# MotorCtrl.net
KiCad netlist of a schematic drawn in Altium Designer
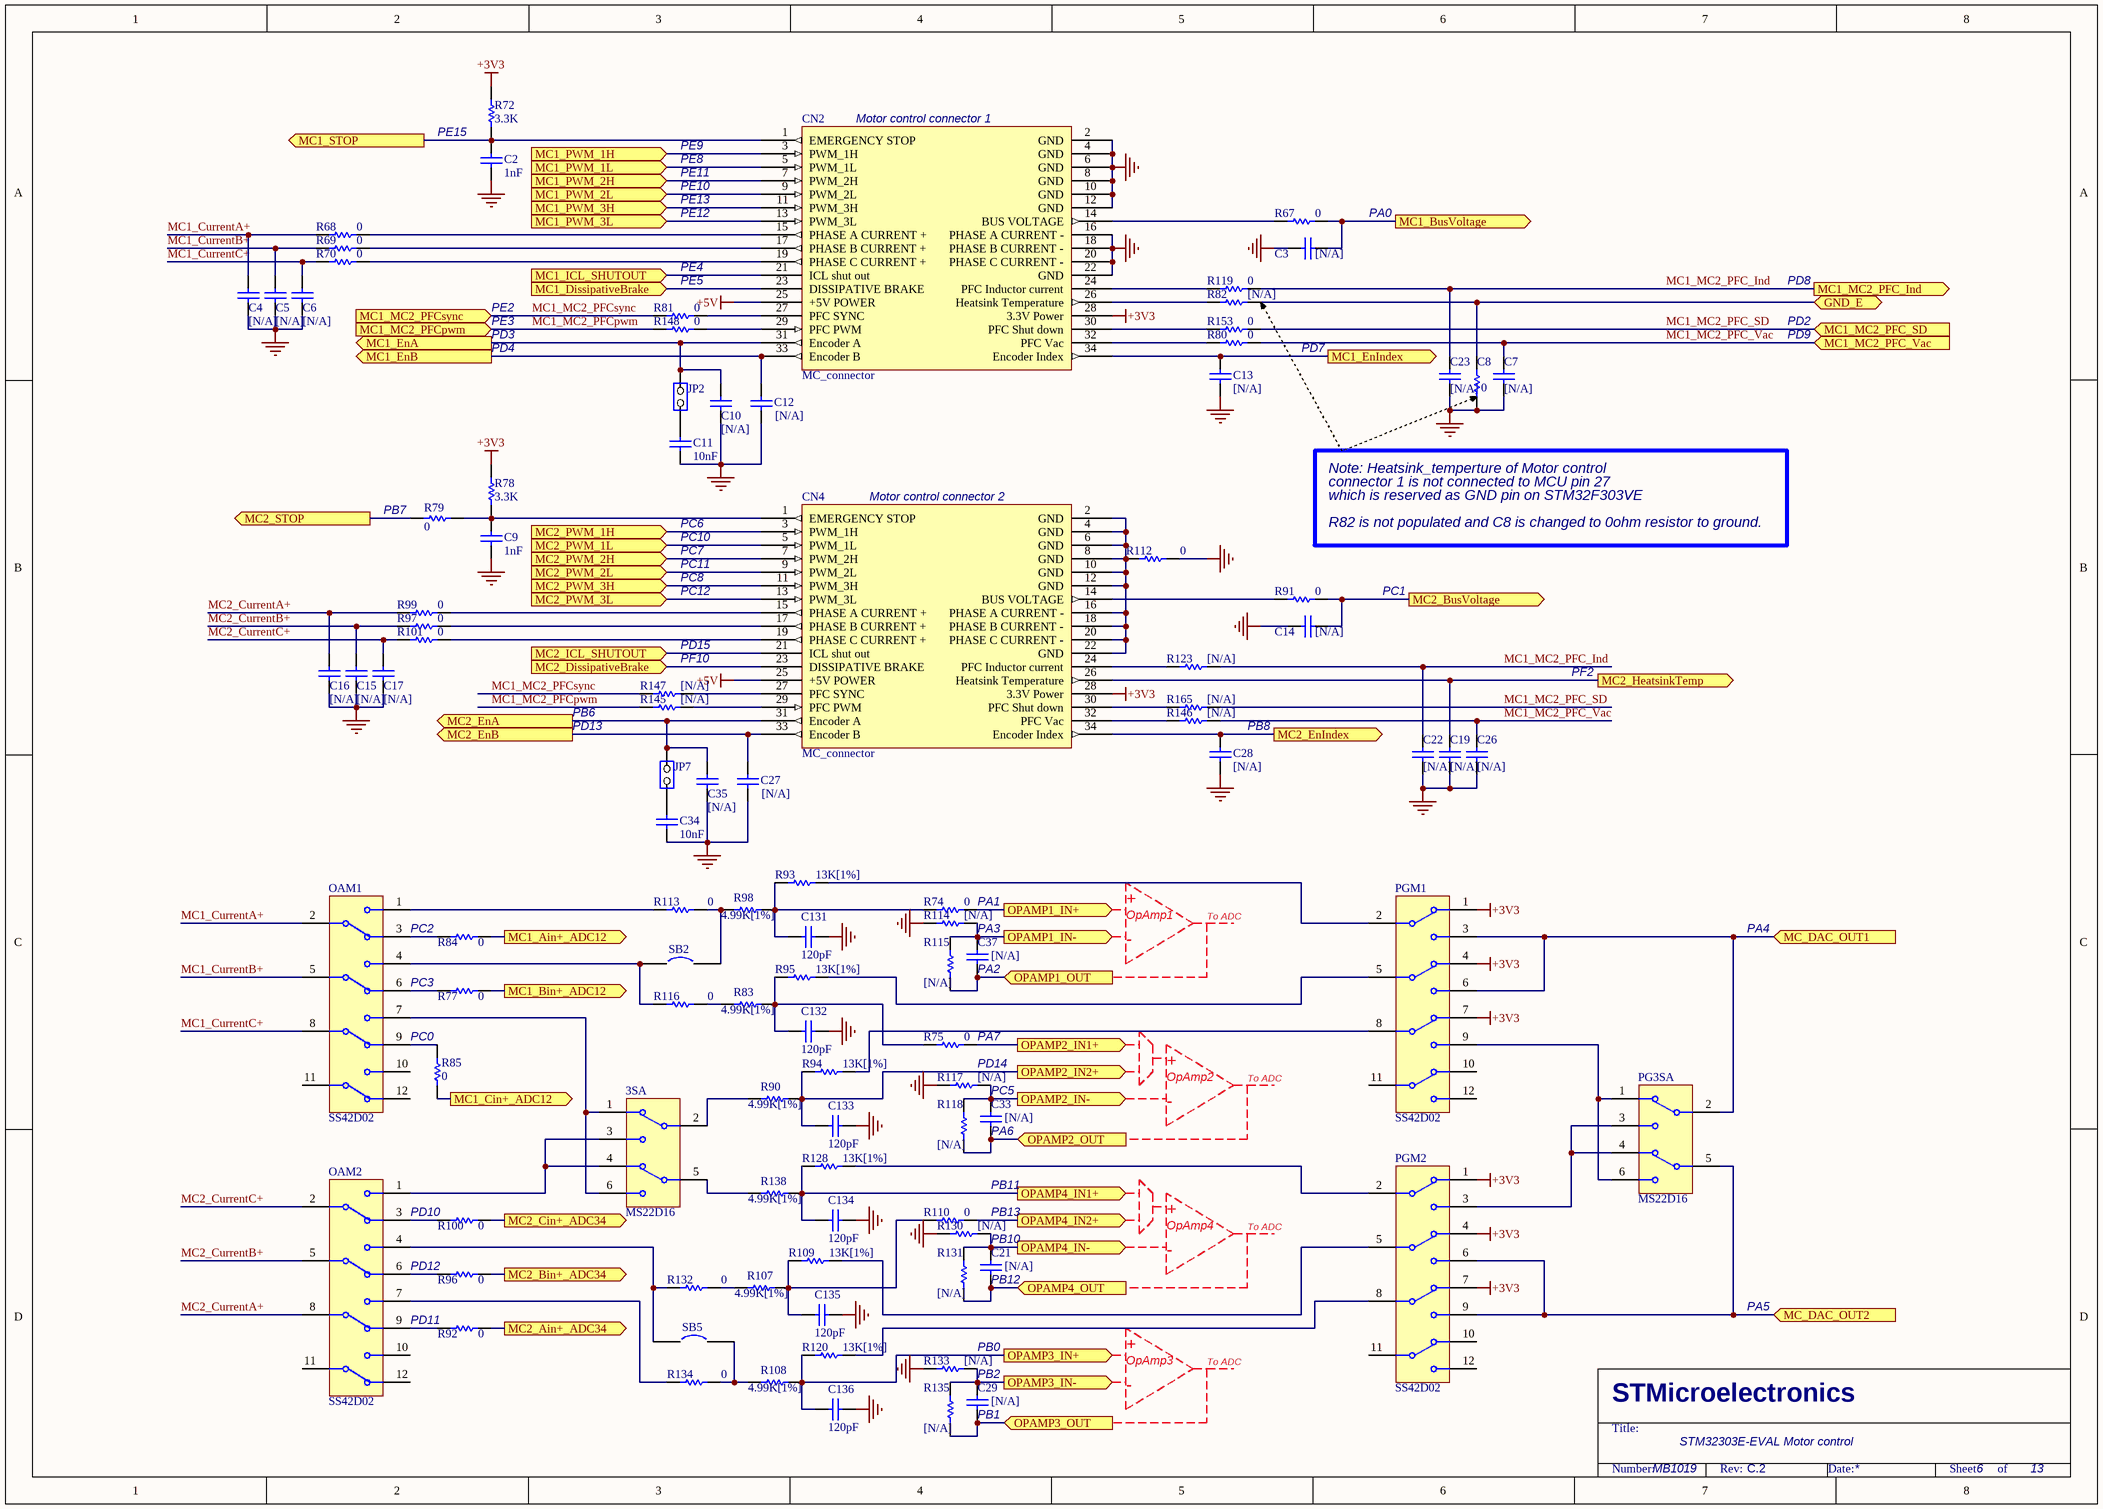
[diagram p0: MotorCtrl.SchDoc]

(export (version "E")
  (design (tool "Eeschema 10.0.6"))
  (components
    (comp (ref "3SA")
      (value "MS22D16")
      (footprint "MS22D16")
      (description "DPDT")
      (fields (field (name "PUBLISHER") "Altium Limited"))
      (libsource (lib "MB1019") (part "MS22D16"))
    )
    (comp (ref "C2")
      (value "1nF")
      (footprint "0603C")
      (description "Capacitor")
      (fields (field (name "PUBLISHER") "Altium Limited"))
      (libsource (lib "Miscellaneous Devices") (part "CAP"))
    )
    (comp (ref "C3")
      (value "[N/A]")
      (footprint "0603C")
      (description "Capacitor")
      (fields (field (name "PUBLISHER") "Altium Limited"))
      (libsource (lib "Miscellaneous Devices") (part "cap"))
    )
    (comp (ref "C4")
      (value "[N/A]")
      (footprint "0603C")
      (description "Capacitor")
      (fields (field (name "PUBLISHER") "Altium Limited"))
      (libsource (lib "Miscellaneous Devices") (part "cap"))
    )
    (comp (ref "C5")
      (value "[N/A]")
      (footprint "0603C")
      (description "Capacitor")
      (fields (field (name "PUBLISHER") "Altium Limited"))
      (libsource (lib "Miscellaneous Devices") (part "cap"))
    )
    (comp (ref "C6")
      (value "[N/A]")
      (footprint "0603C")
      (description "Capacitor")
      (fields (field (name "PUBLISHER") "Altium Limited"))
      (libsource (lib "Miscellaneous Devices") (part "cap"))
    )
    (comp (ref "C7")
      (value "[N/A]")
      (footprint "0603C")
      (description "Capacitor")
      (fields (field (name "PUBLISHER") "Altium Limited"))
      (libsource (lib "Miscellaneous Devices") (part "cap"))
    )
    (comp (ref "C8")
      (value "0")
      (footprint "0603R")
      (description "Resistor")
      (fields (field (name "PUBLISHER") "Altium Limited"))
      (libsource (lib "Miscellaneous Devices") (part "Res1"))
    )
    (comp (ref "C9")
      (value "1nF")
      (footprint "0603C")
      (description "Capacitor")
      (fields (field (name "PUBLISHER") "Altium Limited"))
      (libsource (lib "Miscellaneous Devices") (part "CAP"))
    )
    (comp (ref "C10")
      (value "[N/A]")
      (footprint "0603C")
      (description "Capacitor")
      (fields (field (name "PUBLISHER") "Altium Limited"))
      (libsource (lib "Miscellaneous Devices") (part "cap"))
    )
    (comp (ref "C11")
      (value "10nF")
      (footprint "0603C")
      (description "Capacitor")
      (fields (field (name "PUBLISHER") "Altium Limited"))
      (libsource (lib "Miscellaneous Devices") (part "cap"))
    )
    (comp (ref "C12")
      (value "[N/A]")
      (footprint "0603C")
      (description "Capacitor")
      (fields (field (name "PUBLISHER") "Altium Limited"))
      (libsource (lib "Miscellaneous Devices") (part "cap"))
    )
    (comp (ref "C13")
      (value "[N/A]")
      (footprint "0603C")
      (description "Capacitor")
      (fields (field (name "PUBLISHER") "Altium Limited"))
      (libsource (lib "Miscellaneous Devices") (part "cap"))
    )
    (comp (ref "C14")
      (value "[N/A]")
      (footprint "0603C")
      (description "Capacitor")
      (fields (field (name "PUBLISHER") "Altium Limited"))
      (libsource (lib "Miscellaneous Devices") (part "cap"))
    )
    (comp (ref "C15")
      (value "[N/A]")
      (footprint "0603C")
      (description "Capacitor")
      (fields (field (name "PUBLISHER") "Altium Limited"))
      (libsource (lib "Miscellaneous Devices") (part "cap"))
    )
    (comp (ref "C16")
      (value "[N/A]")
      (footprint "0603C")
      (description "Capacitor")
      (fields (field (name "PUBLISHER") "Altium Limited"))
      (libsource (lib "Miscellaneous Devices") (part "cap"))
    )
    (comp (ref "C17")
      (value "[N/A]")
      (footprint "0603C")
      (description "Capacitor")
      (fields (field (name "PUBLISHER") "Altium Limited"))
      (libsource (lib "Miscellaneous Devices") (part "cap"))
    )
    (comp (ref "C19")
      (value "[N/A]")
      (footprint "0603C")
      (description "Capacitor")
      (fields (field (name "PUBLISHER") "Altium Limited"))
      (libsource (lib "Miscellaneous Devices") (part "cap"))
    )
    (comp (ref "C21")
      (value "[N/A]")
      (footprint "0603C")
      (description "Capacitor")
      (fields (field (name "PUBLISHER") "Altium Limited"))
      (libsource (lib "Miscellaneous Devices") (part "cap"))
    )
    (comp (ref "C22")
      (value "[N/A]")
      (footprint "0603C")
      (description "Capacitor")
      (fields (field (name "PUBLISHER") "Altium Limited"))
      (libsource (lib "Miscellaneous Devices") (part "cap"))
    )
    (comp (ref "C23")
      (value "[N/A]")
      (footprint "0603C")
      (description "Capacitor")
      (fields (field (name "PUBLISHER") "Altium Limited"))
      (libsource (lib "Miscellaneous Devices") (part "cap"))
    )
    (comp (ref "C26")
      (value "[N/A]")
      (footprint "0603C")
      (description "Capacitor")
      (fields (field (name "PUBLISHER") "Altium Limited"))
      (libsource (lib "Miscellaneous Devices") (part "cap"))
    )
    (comp (ref "C27")
      (value "[N/A]")
      (footprint "0603C")
      (description "Capacitor")
      (fields (field (name "PUBLISHER") "Altium Limited"))
      (libsource (lib "Miscellaneous Devices") (part "cap"))
    )
    (comp (ref "C28")
      (value "[N/A]")
      (footprint "0603C")
      (description "Capacitor")
      (fields (field (name "PUBLISHER") "Altium Limited"))
      (libsource (lib "Miscellaneous Devices") (part "cap"))
    )
    (comp (ref "C29")
      (value "[N/A]")
      (footprint "0603C")
      (description "Capacitor")
      (fields (field (name "PUBLISHER") "Altium Limited"))
      (libsource (lib "Miscellaneous Devices") (part "cap"))
    )
    (comp (ref "C33")
      (value "[N/A]")
      (footprint "0603C")
      (description "Capacitor")
      (fields (field (name "PUBLISHER") "Altium Limited"))
      (libsource (lib "Miscellaneous Devices") (part "cap"))
    )
    (comp (ref "C34")
      (value "10nF")
      (footprint "0603C")
      (description "Capacitor")
      (fields (field (name "PUBLISHER") "Altium Limited"))
      (libsource (lib "Miscellaneous Devices") (part "cap"))
    )
    (comp (ref "C35")
      (value "[N/A]")
      (footprint "0603C")
      (description "Capacitor")
      (fields (field (name "PUBLISHER") "Altium Limited"))
      (libsource (lib "Miscellaneous Devices") (part "cap"))
    )
    (comp (ref "C37")
      (value "[N/A]")
      (footprint "0603C")
      (description "Capacitor")
      (fields (field (name "PUBLISHER") "Altium Limited"))
      (libsource (lib "Miscellaneous Devices") (part "cap"))
    )
    (comp (ref "C131")
      (value "120pF")
      (footprint "0603C")
      (description "Capacitor")
      (fields (field (name "PUBLISHER") "Altium Limited"))
      (libsource (lib "Miscellaneous Devices") (part "cap"))
    )
    (comp (ref "C132")
      (value "120pF")
      (footprint "0603C")
      (description "Capacitor")
      (fields (field (name "PUBLISHER") "Altium Limited"))
      (libsource (lib "Miscellaneous Devices") (part "cap"))
    )
    (comp (ref "C133")
      (value "120pF")
      (footprint "0603C")
      (description "Capacitor")
      (fields (field (name "PUBLISHER") "Altium Limited"))
      (libsource (lib "Miscellaneous Devices") (part "cap"))
    )
    (comp (ref "C134")
      (value "120pF")
      (footprint "0603C")
      (description "Capacitor")
      (fields (field (name "PUBLISHER") "Altium Limited"))
      (libsource (lib "Miscellaneous Devices") (part "cap"))
    )
    (comp (ref "C135")
      (value "120pF")
      (footprint "0603C")
      (description "Capacitor")
      (fields (field (name "PUBLISHER") "Altium Limited"))
      (libsource (lib "Miscellaneous Devices") (part "cap"))
    )
    (comp (ref "C136")
      (value "120pF")
      (footprint "0603C")
      (description "Capacitor")
      (fields (field (name "PUBLISHER") "Altium Limited"))
      (libsource (lib "Miscellaneous Devices") (part "cap"))
    )
    (comp (ref "CN2")
      (value "MC_connector")
      (footprint "IDC34S")
      (libsource (lib "MB1019") (part "MC_connector_1"))
    )
    (comp (ref "CN4")
      (value "MC_connector")
      (footprint "IDC34S")
      (libsource (lib "MB1019") (part "MC_connector_1"))
    )
    (comp (ref "JP2") (value "~") (footprint "SIP2") (libsource (lib "*") (part "JP2")))
    (comp (ref "JP7") (value "~") (footprint "SIP2") (libsource (lib "*") (part "JP2")))
    (comp (ref "OAM1")
      (value "SS42D02")
      (footprint "SS42D02")
      (description "SPDT Subminiature Toggle Switch, Right Angle Mounting, Vertical Actuation")
      (fields (field (name "PUBLISHER") "Altium Limited"))
      (libsource (lib "MB1019") (part "SS42D02_1"))
    )
    (comp (ref "OAM2")
      (value "SS42D02")
      (footprint "SS42D02")
      (description "SPDT Subminiature Toggle Switch, Right Angle Mounting, Vertical Actuation")
      (fields (field (name "PUBLISHER") "Altium Limited"))
      (libsource (lib "MB1019") (part "SS42D02_1"))
    )
    (comp (ref "PG3SA")
      (value "MS22D16")
      (footprint "MS22D16")
      (description "DPDT")
      (fields (field (name "PUBLISHER") "Altium Limited"))
      (libsource (lib "MB1019") (part "MS22D16"))
    )
    (comp (ref "PGM1")
      (value "SS42D02")
      (footprint "SS42D02")
      (description "SPDT Subminiature Toggle Switch, Right Angle Mounting, Vertical Actuation")
      (fields (field (name "PUBLISHER") "Altium Limited"))
      (libsource (lib "MB1019") (part "SS42D02"))
    )
    (comp (ref "PGM2")
      (value "SS42D02")
      (footprint "SS42D02")
      (description "SPDT Subminiature Toggle Switch, Right Angle Mounting, Vertical Actuation")
      (fields (field (name "PUBLISHER") "Altium Limited"))
      (libsource (lib "MB1019") (part "SS42D02"))
    )
    (comp (ref "R67")
      (value "0")
      (footprint "0603R")
      (description "Resistor")
      (fields (field (name "PUBLISHER") "Altium Limited"))
      (libsource (lib "Miscellaneous Devices") (part "Res1"))
    )
    (comp (ref "R68")
      (value "0")
      (footprint "0603R")
      (description "Resistor")
      (fields (field (name "PUBLISHER") "Altium Limited"))
      (libsource (lib "Miscellaneous Devices") (part "Res1"))
    )
    (comp (ref "R69")
      (value "0")
      (footprint "0603R")
      (description "Resistor")
      (fields (field (name "PUBLISHER") "Altium Limited"))
      (libsource (lib "Miscellaneous Devices") (part "Res1"))
    )
    (comp (ref "R70")
      (value "0")
      (footprint "0603R")
      (description "Resistor")
      (fields (field (name "PUBLISHER") "Altium Limited"))
      (libsource (lib "Miscellaneous Devices") (part "Res1"))
    )
    (comp (ref "R72")
      (value "3.3K")
      (footprint "0603R")
      (description "Resistor")
      (fields (field (name "PUBLISHER") "Altium Limited"))
      (libsource (lib "Miscellaneous Devices") (part "Res1"))
    )
    (comp (ref "R74")
      (value "0")
      (footprint "0603R")
      (description "Resistor")
      (fields (field (name "PUBLISHER") "Altium Limited"))
      (libsource (lib "Miscellaneous Devices") (part "Res1"))
    )
    (comp (ref "R75")
      (value "0")
      (footprint "0603R")
      (description "Resistor")
      (fields (field (name "PUBLISHER") "Altium Limited"))
      (libsource (lib "Miscellaneous Devices") (part "Res1"))
    )
    (comp (ref "R77")
      (value "0")
      (footprint "0603R")
      (description "Resistor")
      (fields (field (name "PUBLISHER") "Altium Limited"))
      (libsource (lib "Miscellaneous Devices") (part "Res1"))
    )
    (comp (ref "R78")
      (value "3.3K")
      (footprint "0603R")
      (description "Resistor")
      (fields (field (name "PUBLISHER") "Altium Limited"))
      (libsource (lib "Miscellaneous Devices") (part "Res1"))
    )
    (comp (ref "R79")
      (value "0")
      (footprint "0603R")
      (description "Resistor")
      (fields (field (name "PUBLISHER") "Altium Limited"))
      (libsource (lib "Miscellaneous Devices") (part "Res1"))
    )
    (comp (ref "R80")
      (value "0")
      (footprint "0603R")
      (description "Resistor")
      (fields (field (name "PUBLISHER") "Altium Limited"))
      (libsource (lib "Miscellaneous Devices") (part "Res1"))
    )
    (comp (ref "R81")
      (value "0")
      (footprint "0603R")
      (description "Resistor")
      (fields (field (name "PUBLISHER") "Altium Limited"))
      (libsource (lib "Miscellaneous Devices") (part "Res1"))
    )
    (comp (ref "R82")
      (value "[N/A]")
      (footprint "0603R")
      (description "Resistor")
      (fields (field (name "PUBLISHER") "Altium Limited"))
      (libsource (lib "Miscellaneous Devices") (part "Res1"))
    )
    (comp (ref "R83")
      (value "4.99K[1%]")
      (footprint "0603R")
      (description "Resistor")
      (fields (field (name "PUBLISHER") "Altium Limited"))
      (libsource (lib "Miscellaneous Devices") (part "Res1"))
    )
    (comp (ref "R84")
      (value "0")
      (footprint "0603R")
      (description "Resistor")
      (fields (field (name "PUBLISHER") "Altium Limited"))
      (libsource (lib "Miscellaneous Devices") (part "Res1"))
    )
    (comp (ref "R85")
      (value "0")
      (footprint "0603R")
      (description "Resistor")
      (fields (field (name "PUBLISHER") "Altium Limited"))
      (libsource (lib "Miscellaneous Devices") (part "Res1"))
    )
    (comp (ref "R90")
      (value "4.99K[1%]")
      (footprint "0603R")
      (description "Resistor")
      (fields (field (name "PUBLISHER") "Altium Limited"))
      (libsource (lib "Miscellaneous Devices") (part "Res1"))
    )
    (comp (ref "R91")
      (value "0")
      (footprint "0603R")
      (description "Resistor")
      (fields (field (name "PUBLISHER") "Altium Limited"))
      (libsource (lib "Miscellaneous Devices") (part "Res1"))
    )
    (comp (ref "R92")
      (value "0")
      (footprint "0603R")
      (description "Resistor")
      (fields (field (name "PUBLISHER") "Altium Limited"))
      (libsource (lib "Miscellaneous Devices") (part "Res1"))
    )
    (comp (ref "R93")
      (value "13K[1%]")
      (footprint "0603R")
      (description "Resistor")
      (fields (field (name "PUBLISHER") "Altium Limited"))
      (libsource (lib "Miscellaneous Devices") (part "Res1"))
    )
    (comp (ref "R94")
      (value "13K[1%]")
      (footprint "0603R")
      (description "Resistor")
      (fields (field (name "PUBLISHER") "Altium Limited"))
      (libsource (lib "Miscellaneous Devices") (part "Res1"))
    )
    (comp (ref "R95")
      (value "13K[1%]")
      (footprint "0603R")
      (description "Resistor")
      (fields (field (name "PUBLISHER") "Altium Limited"))
      (libsource (lib "Miscellaneous Devices") (part "Res1"))
    )
    (comp (ref "R96")
      (value "0")
      (footprint "0603R")
      (description "Resistor")
      (fields (field (name "PUBLISHER") "Altium Limited"))
      (libsource (lib "Miscellaneous Devices") (part "Res1"))
    )
    (comp (ref "R97")
      (value "0")
      (footprint "0603R")
      (description "Resistor")
      (fields (field (name "PUBLISHER") "Altium Limited"))
      (libsource (lib "Miscellaneous Devices") (part "Res1"))
    )
    (comp (ref "R98")
      (value "4.99K[1%]")
      (footprint "0603R")
      (description "Resistor")
      (fields (field (name "PUBLISHER") "Altium Limited"))
      (libsource (lib "Miscellaneous Devices") (part "Res1"))
    )
    (comp (ref "R99")
      (value "0")
      (footprint "0603R")
      (description "Resistor")
      (fields (field (name "PUBLISHER") "Altium Limited"))
      (libsource (lib "Miscellaneous Devices") (part "Res1"))
    )
    (comp (ref "R100")
      (value "0")
      (footprint "0603R")
      (description "Resistor")
      (fields (field (name "PUBLISHER") "Altium Limited"))
      (libsource (lib "Miscellaneous Devices") (part "Res1"))
    )
    (comp (ref "R101")
      (value "0")
      (footprint "0603R")
      (description "Resistor")
      (fields (field (name "PUBLISHER") "Altium Limited"))
      (libsource (lib "Miscellaneous Devices") (part "Res1"))
    )
    (comp (ref "R107")
      (value "4.99K[1%]")
      (footprint "0603R")
      (description "Resistor")
      (fields (field (name "PUBLISHER") "Altium Limited"))
      (libsource (lib "Miscellaneous Devices") (part "Res1"))
    )
    (comp (ref "R108")
      (value "4.99K[1%]")
      (footprint "0603R")
      (description "Resistor")
      (fields (field (name "PUBLISHER") "Altium Limited"))
      (libsource (lib "Miscellaneous Devices") (part "Res1"))
    )
    (comp (ref "R109")
      (value "13K[1%]")
      (footprint "0603R")
      (description "Resistor")
      (fields (field (name "PUBLISHER") "Altium Limited"))
      (libsource (lib "Miscellaneous Devices") (part "Res1"))
    )
    (comp (ref "R110")
      (value "0")
      (footprint "0603R")
      (description "Resistor")
      (fields (field (name "PUBLISHER") "Altium Limited"))
      (libsource (lib "Miscellaneous Devices") (part "Res1"))
    )
    (comp (ref "R112")
      (value "0")
      (footprint "0603R")
      (description "Resistor")
      (fields (field (name "PUBLISHER") "Altium Limited"))
      (libsource (lib "Miscellaneous Devices") (part "Res1"))
    )
    (comp (ref "R113")
      (value "0")
      (footprint "0603R")
      (description "Resistor")
      (fields (field (name "PUBLISHER") "Altium Limited"))
      (libsource (lib "Miscellaneous Devices") (part "Res1"))
    )
    (comp (ref "R114")
      (value "[N/A]")
      (footprint "0603R")
      (description "Resistor")
      (fields (field (name "PUBLISHER") "Altium Limited"))
      (libsource (lib "Miscellaneous Devices") (part "Res1"))
    )
    (comp (ref "R115")
      (value "[N/A]")
      (footprint "0603R")
      (description "Resistor")
      (fields (field (name "PUBLISHER") "Altium Limited"))
      (libsource (lib "Miscellaneous Devices") (part "Res1"))
    )
    (comp (ref "R116")
      (value "0")
      (footprint "0603R")
      (description "Resistor")
      (fields (field (name "PUBLISHER") "Altium Limited"))
      (libsource (lib "Miscellaneous Devices") (part "Res1"))
    )
    (comp (ref "R117")
      (value "[N/A]")
      (footprint "0603R")
      (description "Resistor")
      (fields (field (name "PUBLISHER") "Altium Limited"))
      (libsource (lib "Miscellaneous Devices") (part "Res1"))
    )
    (comp (ref "R118")
      (value "[N/A]")
      (footprint "0603R")
      (description "Resistor")
      (fields (field (name "PUBLISHER") "Altium Limited"))
      (libsource (lib "Miscellaneous Devices") (part "Res1"))
    )
    (comp (ref "R119")
      (value "0")
      (footprint "0603R")
      (description "Resistor")
      (fields (field (name "PUBLISHER") "Altium Limited"))
      (libsource (lib "Miscellaneous Devices") (part "Res1"))
    )
    (comp (ref "R120")
      (value "13K[1%]")
      (footprint "0603R")
      (description "Resistor")
      (fields (field (name "PUBLISHER") "Altium Limited"))
      (libsource (lib "Miscellaneous Devices") (part "Res1"))
    )
    (comp (ref "R123")
      (value "[N/A]")
      (footprint "0603R")
      (description "Resistor")
      (fields (field (name "PUBLISHER") "Altium Limited"))
      (libsource (lib "Miscellaneous Devices") (part "Res1"))
    )
    (comp (ref "R128")
      (value "13K[1%]")
      (footprint "0603R")
      (description "Resistor")
      (fields (field (name "PUBLISHER") "Altium Limited"))
      (libsource (lib "Miscellaneous Devices") (part "Res1"))
    )
    (comp (ref "R130")
      (value "[N/A]")
      (footprint "0603R")
      (description "Resistor")
      (fields (field (name "PUBLISHER") "Altium Limited"))
      (libsource (lib "Miscellaneous Devices") (part "Res1"))
    )
    (comp (ref "R131")
      (value "[N/A]")
      (footprint "0603R")
      (description "Resistor")
      (fields (field (name "PUBLISHER") "Altium Limited"))
      (libsource (lib "Miscellaneous Devices") (part "Res1"))
    )
    (comp (ref "R132")
      (value "0")
      (footprint "0603R")
      (description "Resistor")
      (fields (field (name "PUBLISHER") "Altium Limited"))
      (libsource (lib "Miscellaneous Devices") (part "Res1"))
    )
    (comp (ref "R133")
      (value "[N/A]")
      (footprint "0603R")
      (description "Resistor")
      (fields (field (name "PUBLISHER") "Altium Limited"))
      (libsource (lib "Miscellaneous Devices") (part "Res1"))
    )
    (comp (ref "R134")
      (value "0")
      (footprint "0603R")
      (description "Resistor")
      (fields (field (name "PUBLISHER") "Altium Limited"))
      (libsource (lib "Miscellaneous Devices") (part "Res1"))
    )
    (comp (ref "R135")
      (value "[N/A]")
      (footprint "0603R")
      (description "Resistor")
      (fields (field (name "PUBLISHER") "Altium Limited"))
      (libsource (lib "Miscellaneous Devices") (part "Res1"))
    )
    (comp (ref "R138")
      (value "4.99K[1%]")
      (footprint "0603R")
      (description "Resistor")
      (fields (field (name "PUBLISHER") "Altium Limited"))
      (libsource (lib "Miscellaneous Devices") (part "Res1"))
    )
    (comp (ref "R145")
      (value "[N/A]")
      (footprint "0603R")
      (description "Resistor")
      (fields (field (name "PUBLISHER") "Altium Limited"))
      (libsource (lib "Miscellaneous Devices") (part "Res1"))
    )
    (comp (ref "R146")
      (value "[N/A]")
      (footprint "0603R")
      (description "Resistor")
      (fields (field (name "PUBLISHER") "Altium Limited"))
      (libsource (lib "Miscellaneous Devices") (part "Res1"))
    )
    (comp (ref "R147")
      (value "[N/A]")
      (footprint "0603R")
      (description "Resistor")
      (fields (field (name "PUBLISHER") "Altium Limited"))
      (libsource (lib "Miscellaneous Devices") (part "Res1"))
    )
    (comp (ref "R148")
      (value "0")
      (footprint "0603R")
      (description "Resistor")
      (fields (field (name "PUBLISHER") "Altium Limited"))
      (libsource (lib "Miscellaneous Devices") (part "Res1"))
    )
    (comp (ref "R153")
      (value "0")
      (footprint "0603R")
      (description "Resistor")
      (fields (field (name "PUBLISHER") "Altium Limited"))
      (libsource (lib "Miscellaneous Devices") (part "Res1"))
    )
    (comp (ref "R165")
      (value "[N/A]")
      (footprint "0603R")
      (description "Resistor")
      (fields (field (name "PUBLISHER") "Altium Limited"))
      (libsource (lib "Miscellaneous Devices") (part "Res1"))
    )
    (comp (ref "SB2")
      (value "~")
      (footprint "JP2_SMD")
      (description "Circuit Breaker")
      (fields (field (name "PUBLISHER") "Altium Limited"))
      (libsource (lib "Miscellaneous Devices") (part "Circuit Breaker"))
    )
    (comp (ref "SB5")
      (value "~")
      (footprint "JP2_SMD")
      (description "Circuit Breaker")
      (fields (field (name "PUBLISHER") "Altium Limited"))
      (libsource (lib "Miscellaneous Devices") (part "Circuit Breaker"))
    )
  )
  (nets
    (net (code "1") (name "+3V3") (class "Default")
      (node (ref "CN2") (pin "28") (pinfunction "3.3V_Power_28") (pintype "power_in"))
      (node (ref "CN4") (pin "28") (pinfunction "3.3V_Power_28") (pintype "power_in"))
      (node (ref "PGM1") (pin "1") (pintype "passive"))
      (node (ref "PGM1") (pin "4") (pintype "passive"))
      (node (ref "PGM1") (pin "7") (pintype "passive"))
      (node (ref "PGM2") (pin "1") (pintype "passive"))
      (node (ref "PGM2") (pin "4") (pintype "passive"))
      (node (ref "PGM2") (pin "7") (pintype "passive"))
      (node (ref "R72") (pin "2") (pinfunction "2_2") (pintype "passive"))
      (node (ref "R78") (pin "2") (pinfunction "2_2") (pintype "passive"))
    )
    (net (code "2") (name "+5V") (class "Default")
      (node (ref "CN2") (pin "25") (pinfunction "+5V_POWER_25") (pintype "power_in"))
      (node (ref "CN4") (pin "25") (pinfunction "+5V_POWER_25") (pintype "power_in"))
    )
    (net (code "3") (name "/GND_E") (class "Default")
      (node (ref "C8") (pin "1") (pinfunction "1_1") (pintype "passive"))
      (node (ref "R82") (pin "2") (pinfunction "2_2") (pintype "passive"))
    )
    (net (code "4") (name "/MC1_Ain+_ADC12") (class "Default")
      (node (ref "R84") (pin "1") (pinfunction "1_1") (pintype "passive"))
    )
    (net (code "5") (name "/MC1_Bin+_ADC12") (class "Default")
      (node (ref "R77") (pin "1") (pinfunction "1_1") (pintype "passive"))
    )
    (net (code "6") (name "/MC1_BusVoltage") (class "Default")
      (node (ref "C3") (pin "1") (pinfunction "1_1") (pintype "passive"))
      (node (ref "R67") (pin "1") (pinfunction "1_1") (pintype "passive"))
    )
    (net (code "7") (name "/MC1_Cin+_ADC12") (class "Default")
      (node (ref "R85") (pin "2") (pinfunction "2_2") (pintype "passive"))
    )
    (net (code "8") (name "/MC1_CurrentA+") (class "Default")
      (node (ref "C4") (pin "2") (pinfunction "2_2") (pintype "passive"))
      (node (ref "OAM1") (pin "2") (pintype "passive"))
      (node (ref "R68") (pin "2") (pinfunction "2_2") (pintype "passive"))
    )
    (net (code "9") (name "/MC1_CurrentB+") (class "Default")
      (node (ref "C5") (pin "2") (pinfunction "2_2") (pintype "passive"))
      (node (ref "OAM1") (pin "5") (pintype "passive"))
      (node (ref "R69") (pin "2") (pinfunction "2_2") (pintype "passive"))
    )
    (net (code "10") (name "/MC1_CurrentC+") (class "Default")
      (node (ref "C6") (pin "2") (pinfunction "2_2") (pintype "passive"))
      (node (ref "OAM1") (pin "8") (pintype "passive"))
      (node (ref "R70") (pin "2") (pinfunction "2_2") (pintype "passive"))
    )
    (net (code "11") (name "/MC1_DissipativeBrake") (class "Default")
      (node (ref "CN2") (pin "23") (pinfunction "DISSIPATIVE_BRAKE_23") (pintype "passive"))
    )
    (net (code "12") (name "/MC1_EnA") (class "Default")
      (node (ref "C10") (pin "2") (pinfunction "2_2") (pintype "passive"))
      (node (ref "CN2") (pin "31") (pinfunction "Encoder_A_31") (pintype "output"))
      (node (ref "JP2") (pin "1") (pinfunction "COMMON_1") (pintype "passive"))
    )
    (net (code "13") (name "/MC1_EnB") (class "Default")
      (node (ref "C12") (pin "2") (pinfunction "2_2") (pintype "passive"))
      (node (ref "CN2") (pin "33") (pinfunction "Encoder_B_33") (pintype "output"))
    )
    (net (code "14") (name "/MC1_EnIndex") (class "Default")
      (node (ref "C13") (pin "2") (pinfunction "2_2") (pintype "passive"))
      (node (ref "CN2") (pin "34") (pinfunction "Encoder_Index_34") (pintype "output"))
    )
    (net (code "15") (name "/MC1_ICL_SHUTOUT") (class "Default")
      (node (ref "CN2") (pin "21") (pinfunction "ICL_shut_out_21") (pintype "passive"))
    )
    (net (code "16") (name "/MC1_MC2_PFC_Ind") (class "Default")
      (node (ref "C22") (pin "2") (pinfunction "2_2") (pintype "passive"))
      (node (ref "C23") (pin "2") (pinfunction "2_2") (pintype "passive"))
      (node (ref "R119") (pin "1") (pinfunction "1_1") (pintype "passive"))
      (node (ref "R123") (pin "1") (pinfunction "1_1") (pintype "passive"))
    )
    (net (code "17") (name "/MC1_MC2_PFC_SD") (class "Default")
      (node (ref "R153") (pin "1") (pinfunction "1_1") (pintype "passive"))
      (node (ref "R165") (pin "1") (pinfunction "1_1") (pintype "passive"))
    )
    (net (code "18") (name "/MC1_MC2_PFC_Vac") (class "Default")
      (node (ref "C26") (pin "2") (pinfunction "2_2") (pintype "passive"))
      (node (ref "C7") (pin "2") (pinfunction "2_2") (pintype "passive"))
      (node (ref "R146") (pin "1") (pinfunction "1_1") (pintype "passive"))
      (node (ref "R80") (pin "1") (pinfunction "1_1") (pintype "passive"))
    )
    (net (code "19") (name "/MC1_MC2_PFCpwm") (class "Default")
      (node (ref "R145") (pin "2") (pinfunction "2_2") (pintype "passive"))
      (node (ref "R148") (pin "2") (pinfunction "2_2") (pintype "passive"))
    )
    (net (code "20") (name "/MC1_MC2_PFCsync") (class "Default")
      (node (ref "R147") (pin "2") (pinfunction "2_2") (pintype "passive"))
      (node (ref "R81") (pin "2") (pinfunction "2_2") (pintype "passive"))
    )
    (net (code "21") (name "/MC1_PWM_1H") (class "Default")
      (node (ref "CN2") (pin "3") (pinfunction "PWM_1H_3") (pintype "input"))
    )
    (net (code "22") (name "/MC1_PWM_1L") (class "Default")
      (node (ref "CN2") (pin "5") (pinfunction "PWM_1L_5") (pintype "input"))
    )
    (net (code "23") (name "/MC1_PWM_2H") (class "Default")
      (node (ref "CN2") (pin "7") (pinfunction "PWM_2H_7") (pintype "input"))
    )
    (net (code "24") (name "/MC1_PWM_2L") (class "Default")
      (node (ref "CN2") (pin "9") (pinfunction "PWM_2L_9") (pintype "input"))
    )
    (net (code "25") (name "/MC1_PWM_3H") (class "Default")
      (node (ref "CN2") (pin "11") (pinfunction "PWM_3H_11") (pintype "input"))
    )
    (net (code "26") (name "/MC1_PWM_3L") (class "Default")
      (node (ref "CN2") (pin "13") (pinfunction "PWM_3L_13") (pintype "input"))
    )
    (net (code "27") (name "/MC1_STOP") (class "Default")
      (node (ref "C2") (pin "2") (pinfunction "2_2") (pintype "passive"))
      (node (ref "CN2") (pin "1") (pinfunction "EMERGENCY_STOP_1") (pintype "output"))
      (node (ref "R72") (pin "1") (pinfunction "1_1") (pintype "passive"))
    )
    (net (code "28") (name "/MC2_Ain+_ADC34") (class "Default")
      (node (ref "R92") (pin "1") (pinfunction "1_1") (pintype "passive"))
    )
    (net (code "29") (name "/MC2_Bin+_ADC34") (class "Default")
      (node (ref "R96") (pin "1") (pinfunction "1_1") (pintype "passive"))
    )
    (net (code "30") (name "/MC2_BusVoltage") (class "Default")
      (node (ref "C14") (pin "1") (pinfunction "1_1") (pintype "passive"))
      (node (ref "R91") (pin "1") (pinfunction "1_1") (pintype "passive"))
    )
    (net (code "31") (name "/MC2_Cin+_ADC34") (class "Default")
      (node (ref "R100") (pin "1") (pinfunction "1_1") (pintype "passive"))
    )
    (net (code "32") (name "/MC2_CurrentA+") (class "Default")
      (node (ref "C16") (pin "2") (pinfunction "2_2") (pintype "passive"))
      (node (ref "OAM2") (pin "8") (pintype "passive"))
      (node (ref "R99") (pin "2") (pinfunction "2_2") (pintype "passive"))
    )
    (net (code "33") (name "/MC2_CurrentB+") (class "Default")
      (node (ref "C15") (pin "2") (pinfunction "2_2") (pintype "passive"))
      (node (ref "OAM2") (pin "5") (pintype "passive"))
      (node (ref "R97") (pin "2") (pinfunction "2_2") (pintype "passive"))
    )
    (net (code "34") (name "/MC2_CurrentC+") (class "Default")
      (node (ref "C17") (pin "2") (pinfunction "2_2") (pintype "passive"))
      (node (ref "OAM2") (pin "2") (pintype "passive"))
      (node (ref "R101") (pin "2") (pinfunction "2_2") (pintype "passive"))
    )
    (net (code "35") (name "/MC2_DissipativeBrake") (class "Default")
      (node (ref "CN4") (pin "23") (pinfunction "DISSIPATIVE_BRAKE_23") (pintype "passive"))
    )
    (net (code "36") (name "/MC2_EnA") (class "Default")
      (node (ref "C35") (pin "2") (pinfunction "2_2") (pintype "passive"))
      (node (ref "CN4") (pin "31") (pinfunction "Encoder_A_31") (pintype "output"))
      (node (ref "JP7") (pin "1") (pinfunction "COMMON_1") (pintype "passive"))
    )
    (net (code "37") (name "/MC2_EnB") (class "Default")
      (node (ref "C27") (pin "2") (pinfunction "2_2") (pintype "passive"))
      (node (ref "CN4") (pin "33") (pinfunction "Encoder_B_33") (pintype "output"))
    )
    (net (code "38") (name "/MC2_EnIndex") (class "Default")
      (node (ref "C28") (pin "2") (pinfunction "2_2") (pintype "passive"))
      (node (ref "CN4") (pin "34") (pinfunction "Encoder_Index_34") (pintype "output"))
    )
    (net (code "39") (name "/MC2_HeatsinkTemp") (class "Default")
      (node (ref "C19") (pin "2") (pinfunction "2_2") (pintype "passive"))
      (node (ref "CN4") (pin "26") (pinfunction "Heatsink_Temperature_26") (pintype "output"))
    )
    (net (code "40") (name "/MC2_ICL_SHUTOUT") (class "Default")
      (node (ref "CN4") (pin "21") (pinfunction "ICL_shut_out_21") (pintype "passive"))
    )
    (net (code "41") (name "/MC2_PWM_1H") (class "Default")
      (node (ref "CN4") (pin "3") (pinfunction "PWM_1H_3") (pintype "input"))
    )
    (net (code "42") (name "/MC2_PWM_1L") (class "Default")
      (node (ref "CN4") (pin "5") (pinfunction "PWM_1L_5") (pintype "input"))
    )
    (net (code "43") (name "/MC2_PWM_2H") (class "Default")
      (node (ref "CN4") (pin "7") (pinfunction "PWM_2H_7") (pintype "input"))
    )
    (net (code "44") (name "/MC2_PWM_2L") (class "Default")
      (node (ref "CN4") (pin "9") (pinfunction "PWM_2L_9") (pintype "input"))
    )
    (net (code "45") (name "/MC2_PWM_3H") (class "Default")
      (node (ref "CN4") (pin "11") (pinfunction "PWM_3H_11") (pintype "input"))
    )
    (net (code "46") (name "/MC2_PWM_3L") (class "Default")
      (node (ref "CN4") (pin "13") (pinfunction "PWM_3L_13") (pintype "input"))
    )
    (net (code "47") (name "/MC2_STOP") (class "Default")
      (node (ref "R79") (pin "2") (pinfunction "2_2") (pintype "passive"))
    )
    (net (code "48") (name "/MC_DAC_OUT1") (class "Default")
      (node (ref "PG3SA") (pin "2") (pintype "passive"))
      (node (ref "PGM1") (pin "3") (pintype "passive"))
      (node (ref "PGM1") (pin "6") (pintype "passive"))
    )
    (net (code "49") (name "/MC_DAC_OUT2") (class "Default")
      (node (ref "PG3SA") (pin "5") (pintype "passive"))
      (node (ref "PGM2") (pin "6") (pintype "passive"))
      (node (ref "PGM2") (pin "9") (pintype "passive"))
    )
    (net (code "50") (name "/OPAMP1_IN+") (class "Default")
      (node (ref "R74") (pin "1") (pinfunction "1_1") (pintype "passive"))
    )
    (net (code "51") (name "/OPAMP1_IN-") (class "Default")
      (node (ref "C37") (pin "2") (pinfunction "2_2") (pintype "passive"))
      (node (ref "R114") (pin "2") (pinfunction "2_2") (pintype "passive"))
      (node (ref "R115") (pin "2") (pinfunction "2_2") (pintype "passive"))
    )
    (net (code "52") (name "/OPAMP1_OUT") (class "Default")
      (node (ref "C37") (pin "1") (pinfunction "1_1") (pintype "passive"))
      (node (ref "R115") (pin "1") (pinfunction "1_1") (pintype "passive"))
    )
    (net (code "53") (name "/OPAMP2_IN-") (class "Default")
      (node (ref "C33") (pin "2") (pinfunction "2_2") (pintype "passive"))
      (node (ref "R117") (pin "2") (pinfunction "2_2") (pintype "passive"))
      (node (ref "R118") (pin "2") (pinfunction "2_2") (pintype "passive"))
    )
    (net (code "54") (name "/OPAMP2_IN1+") (class "Default")
      (node (ref "R75") (pin "1") (pinfunction "1_1") (pintype "passive"))
    )
    (net (code "55") (name "/OPAMP2_IN2+") (class "Default")
      (node (ref "C133") (pin "1") (pinfunction "1_1") (pintype "passive"))
      (node (ref "R90") (pin "2") (pinfunction "2_2") (pintype "passive"))
      (node (ref "R94") (pin "1") (pinfunction "1_1") (pintype "passive"))
    )
    (net (code "56") (name "/OPAMP2_OUT") (class "Default")
      (node (ref "C33") (pin "1") (pinfunction "1_1") (pintype "passive"))
      (node (ref "R118") (pin "1") (pinfunction "1_1") (pintype "passive"))
    )
    (net (code "57") (name "/OPAMP3_IN+") (class "Default")
      (node (ref "C136") (pin "1") (pinfunction "1_1") (pintype "passive"))
      (node (ref "R108") (pin "2") (pinfunction "2_2") (pintype "passive"))
      (node (ref "R120") (pin "1") (pinfunction "1_1") (pintype "passive"))
    )
    (net (code "58") (name "/OPAMP3_IN-") (class "Default")
      (node (ref "C29") (pin "2") (pinfunction "2_2") (pintype "passive"))
      (node (ref "R133") (pin "2") (pinfunction "2_2") (pintype "passive"))
      (node (ref "R135") (pin "2") (pinfunction "2_2") (pintype "passive"))
    )
    (net (code "59") (name "/OPAMP3_OUT") (class "Default")
      (node (ref "C29") (pin "1") (pinfunction "1_1") (pintype "passive"))
      (node (ref "R135") (pin "1") (pinfunction "1_1") (pintype "passive"))
    )
    (net (code "60") (name "/OPAMP4_IN-") (class "Default")
      (node (ref "C21") (pin "2") (pinfunction "2_2") (pintype "passive"))
      (node (ref "R130") (pin "2") (pinfunction "2_2") (pintype "passive"))
      (node (ref "R131") (pin "2") (pinfunction "2_2") (pintype "passive"))
    )
    (net (code "61") (name "/OPAMP4_IN1+") (class "Default")
      (node (ref "C134") (pin "1") (pinfunction "1_1") (pintype "passive"))
      (node (ref "R128") (pin "1") (pinfunction "1_1") (pintype "passive"))
      (node (ref "R138") (pin "2") (pinfunction "2_2") (pintype "passive"))
    )
    (net (code "62") (name "/OPAMP4_IN2+") (class "Default")
      (node (ref "R110") (pin "1") (pinfunction "1_1") (pintype "passive"))
    )
    (net (code "63") (name "/OPAMP4_OUT") (class "Default")
      (node (ref "C21") (pin "1") (pinfunction "1_1") (pintype "passive"))
      (node (ref "R131") (pin "1") (pinfunction "1_1") (pintype "passive"))
    )
    (net (code "64") (name "GND") (class "Default")
      (node (ref "C10") (pin "1") (pinfunction "1_1") (pintype "passive"))
      (node (ref "C11") (pin "1") (pinfunction "1_1") (pintype "passive"))
      (node (ref "C12") (pin "1") (pinfunction "1_1") (pintype "passive"))
      (node (ref "C13") (pin "1") (pinfunction "1_1") (pintype "passive"))
      (node (ref "C131") (pin "2") (pinfunction "2_2") (pintype "passive"))
      (node (ref "C132") (pin "2") (pinfunction "2_2") (pintype "passive"))
      (node (ref "C133") (pin "2") (pinfunction "2_2") (pintype "passive"))
      (node (ref "C134") (pin "2") (pinfunction "2_2") (pintype "passive"))
      (node (ref "C135") (pin "2") (pinfunction "2_2") (pintype "passive"))
      (node (ref "C136") (pin "2") (pinfunction "2_2") (pintype "passive"))
      (node (ref "C14") (pin "2") (pinfunction "2_2") (pintype "passive"))
      (node (ref "C15") (pin "1") (pinfunction "1_1") (pintype "passive"))
      (node (ref "C16") (pin "1") (pinfunction "1_1") (pintype "passive"))
      (node (ref "C17") (pin "1") (pinfunction "1_1") (pintype "passive"))
      (node (ref "C19") (pin "1") (pinfunction "1_1") (pintype "passive"))
      (node (ref "C2") (pin "1") (pinfunction "1_1") (pintype "passive"))
      (node (ref "C22") (pin "1") (pinfunction "1_1") (pintype "passive"))
      (node (ref "C23") (pin "1") (pinfunction "1_1") (pintype "passive"))
      (node (ref "C26") (pin "1") (pinfunction "1_1") (pintype "passive"))
      (node (ref "C27") (pin "1") (pinfunction "1_1") (pintype "passive"))
      (node (ref "C28") (pin "1") (pinfunction "1_1") (pintype "passive"))
      (node (ref "C3") (pin "2") (pinfunction "2_2") (pintype "passive"))
      (node (ref "C34") (pin "1") (pinfunction "1_1") (pintype "passive"))
      (node (ref "C35") (pin "1") (pinfunction "1_1") (pintype "passive"))
      (node (ref "C4") (pin "1") (pinfunction "1_1") (pintype "passive"))
      (node (ref "C5") (pin "1") (pinfunction "1_1") (pintype "passive"))
      (node (ref "C6") (pin "1") (pinfunction "1_1") (pintype "passive"))
      (node (ref "C7") (pin "1") (pinfunction "1_1") (pintype "passive"))
      (node (ref "C8") (pin "2") (pinfunction "2_2") (pintype "passive"))
      (node (ref "C9") (pin "1") (pinfunction "1_1") (pintype "passive"))
      (node (ref "CN2") (pin "10") (pinfunction "GND_10") (pintype "power_in"))
      (node (ref "CN2") (pin "12") (pinfunction "GND_12") (pintype "power_in"))
      (node (ref "CN2") (pin "16") (pinfunction "PHASE_A_CURRENT_-_16") (pintype "power_in"))
      (node (ref "CN2") (pin "18") (pinfunction "PHASE_B_CURRENT_-_18") (pintype "power_in"))
      (node (ref "CN2") (pin "2") (pinfunction "GND_2") (pintype "power_in"))
      (node (ref "CN2") (pin "20") (pinfunction "PHASE_C_CURRENT_-_20") (pintype "power_in"))
      (node (ref "CN2") (pin "22") (pinfunction "GND_22") (pintype "power_in"))
      (node (ref "CN2") (pin "4") (pinfunction "GND_4") (pintype "power_in"))
      (node (ref "CN2") (pin "6") (pinfunction "GND_6") (pintype "power_in"))
      (node (ref "CN2") (pin "8") (pinfunction "GND_8") (pintype "power_in"))
      (node (ref "R112") (pin "1") (pinfunction "1_1") (pintype "passive"))
      (node (ref "R114") (pin "1") (pinfunction "1_1") (pintype "passive"))
      (node (ref "R117") (pin "1") (pinfunction "1_1") (pintype "passive"))
      (node (ref "R130") (pin "1") (pinfunction "1_1") (pintype "passive"))
      (node (ref "R133") (pin "1") (pinfunction "1_1") (pintype "passive"))
    )
    (net (code "65") (name "Net-(3SA-Pad1)") (class "Default")
      (node (ref "3SA") (pin "1") (pintype "passive"))
      (node (ref "3SA") (pin "6") (pintype "passive"))
      (node (ref "OAM1") (pin "7") (pintype "passive"))
    )
    (net (code "66") (name "Net-(3SA-Pad2)") (class "Default")
      (node (ref "3SA") (pin "2") (pintype "passive"))
      (node (ref "R90") (pin "1") (pinfunction "1_1") (pintype "passive"))
    )
    (net (code "67") (name "Net-(3SA-Pad3)") (class "Default")
      (node (ref "3SA") (pin "3") (pintype "passive"))
      (node (ref "3SA") (pin "4") (pintype "passive"))
      (node (ref "OAM2") (pin "1") (pintype "passive"))
    )
    (net (code "68") (name "Net-(3SA-Pad5)") (class "Default")
      (node (ref "3SA") (pin "5") (pintype "passive"))
      (node (ref "R138") (pin "1") (pinfunction "1_1") (pintype "passive"))
    )
    (net (code "69") (name "Net-(C131-Pad1)") (class "Default")
      (node (ref "C131") (pin "1") (pinfunction "1_1") (pintype "passive"))
      (node (ref "R74") (pin "2") (pinfunction "2_2") (pintype "passive"))
      (node (ref "R93") (pin "1") (pinfunction "1_1") (pintype "passive"))
      (node (ref "R98") (pin "2") (pinfunction "2_2") (pintype "passive"))
    )
    (net (code "70") (name "Net-(C132-Pad1)") (class "Default")
      (node (ref "C132") (pin "1") (pinfunction "1_1") (pintype "passive"))
      (node (ref "R75") (pin "2") (pinfunction "2_2") (pintype "passive"))
      (node (ref "R83") (pin "2") (pinfunction "2_2") (pintype "passive"))
      (node (ref "R95") (pin "1") (pinfunction "1_1") (pintype "passive"))
    )
    (net (code "71") (name "Net-(C135-Pad1)") (class "Default")
      (node (ref "C135") (pin "1") (pinfunction "1_1") (pintype "passive"))
      (node (ref "R107") (pin "2") (pinfunction "2_2") (pintype "passive"))
      (node (ref "R109") (pin "1") (pinfunction "1_1") (pintype "passive"))
      (node (ref "R110") (pin "2") (pinfunction "2_2") (pintype "passive"))
    )
    (net (code "72") (name "Net-(CN2-BUS_VOLTAGE)") (class "Default")
      (node (ref "CN2") (pin "14") (pinfunction "BUS_VOLTAGE_14") (pintype "output"))
      (node (ref "R67") (pin "2") (pinfunction "2_2") (pintype "passive"))
    )
    (net (code "73") (name "Net-(CN2-Heatsink_Temperature)") (class "Default")
      (node (ref "CN2") (pin "26") (pinfunction "Heatsink_Temperature_26") (pintype "output"))
      (node (ref "R82") (pin "1") (pinfunction "1_1") (pintype "passive"))
    )
    (net (code "74") (name "Net-(CN2-PFC_Inductor_current)") (class "Default")
      (node (ref "CN2") (pin "24") (pinfunction "PFC_Inductor_current_24") (pintype "passive"))
      (node (ref "R119") (pin "2") (pinfunction "2_2") (pintype "passive"))
    )
    (net (code "75") (name "Net-(CN2-PFC_PWM)") (class "Default")
      (node (ref "CN2") (pin "29") (pinfunction "PFC_PWM_29") (pintype "input"))
      (node (ref "R148") (pin "1") (pinfunction "1_1") (pintype "passive"))
    )
    (net (code "76") (name "Net-(CN2-PFC_SYNC)") (class "Default")
      (node (ref "CN2") (pin "27") (pinfunction "PFC_SYNC_27") (pintype "passive"))
      (node (ref "R81") (pin "1") (pinfunction "1_1") (pintype "passive"))
    )
    (net (code "77") (name "Net-(CN2-PFC_Shut_down)") (class "Default")
      (node (ref "CN2") (pin "30") (pinfunction "PFC_Shut_down_30") (pintype "passive"))
      (node (ref "R153") (pin "2") (pinfunction "2_2") (pintype "passive"))
    )
    (net (code "78") (name "Net-(CN2-PFC_Vac)") (class "Default")
      (node (ref "CN2") (pin "32") (pinfunction "PFC_Vac_32") (pintype "passive"))
      (node (ref "R80") (pin "2") (pinfunction "2_2") (pintype "passive"))
    )
    (net (code "79") (name "Net-(CN2-PHASE_A_CURRENT_+)") (class "Default")
      (node (ref "CN2") (pin "15") (pinfunction "PHASE_A_CURRENT_+_15") (pintype "output"))
      (node (ref "R68") (pin "1") (pinfunction "1_1") (pintype "passive"))
    )
    (net (code "80") (name "Net-(CN2-PHASE_B_CURRENT_+)") (class "Default")
      (node (ref "CN2") (pin "17") (pinfunction "PHASE_B_CURRENT_+_17") (pintype "output"))
      (node (ref "R69") (pin "1") (pinfunction "1_1") (pintype "passive"))
    )
    (net (code "81") (name "Net-(CN2-PHASE_C_CURRENT_+)") (class "Default")
      (node (ref "CN2") (pin "19") (pinfunction "PHASE_C_CURRENT_+_19") (pintype "output"))
      (node (ref "R70") (pin "1") (pinfunction "1_1") (pintype "passive"))
    )
    (net (code "82") (name "Net-(CN4-BUS_VOLTAGE)") (class "Default")
      (node (ref "CN4") (pin "14") (pinfunction "BUS_VOLTAGE_14") (pintype "output"))
      (node (ref "R91") (pin "2") (pinfunction "2_2") (pintype "passive"))
    )
    (net (code "83") (name "Net-(CN4-EMERGENCY_STOP)") (class "Default")
      (node (ref "C9") (pin "2") (pinfunction "2_2") (pintype "passive"))
      (node (ref "CN4") (pin "1") (pinfunction "EMERGENCY_STOP_1") (pintype "output"))
      (node (ref "R78") (pin "1") (pinfunction "1_1") (pintype "passive"))
      (node (ref "R79") (pin "1") (pinfunction "1_1") (pintype "passive"))
    )
    (net (code "84") (name "Net-(CN4-PFC_Inductor_current)") (class "Default")
      (node (ref "CN4") (pin "24") (pinfunction "PFC_Inductor_current_24") (pintype "passive"))
      (node (ref "R123") (pin "2") (pinfunction "2_2") (pintype "passive"))
    )
    (net (code "85") (name "Net-(CN4-PFC_PWM)") (class "Default")
      (node (ref "CN4") (pin "29") (pinfunction "PFC_PWM_29") (pintype "input"))
      (node (ref "R145") (pin "1") (pinfunction "1_1") (pintype "passive"))
    )
    (net (code "86") (name "Net-(CN4-PFC_SYNC)") (class "Default")
      (node (ref "CN4") (pin "27") (pinfunction "PFC_SYNC_27") (pintype "passive"))
      (node (ref "R147") (pin "1") (pinfunction "1_1") (pintype "passive"))
    )
    (net (code "87") (name "Net-(CN4-PFC_Shut_down)") (class "Default")
      (node (ref "CN4") (pin "30") (pinfunction "PFC_Shut_down_30") (pintype "passive"))
      (node (ref "R165") (pin "2") (pinfunction "2_2") (pintype "passive"))
    )
    (net (code "88") (name "Net-(CN4-PFC_Vac)") (class "Default")
      (node (ref "CN4") (pin "32") (pinfunction "PFC_Vac_32") (pintype "passive"))
      (node (ref "R146") (pin "2") (pinfunction "2_2") (pintype "passive"))
    )
    (net (code "89") (name "Net-(CN4-PHASE_A_CURRENT_+)") (class "Default")
      (node (ref "CN4") (pin "15") (pinfunction "PHASE_A_CURRENT_+_15") (pintype "output"))
      (node (ref "R99") (pin "1") (pinfunction "1_1") (pintype "passive"))
    )
    (net (code "90") (name "Net-(CN4-PHASE_A_CURRENT_-)") (class "Default")
      (node (ref "CN4") (pin "10") (pinfunction "GND_10") (pintype "power_in"))
      (node (ref "CN4") (pin "12") (pinfunction "GND_12") (pintype "power_in"))
      (node (ref "CN4") (pin "16") (pinfunction "PHASE_A_CURRENT_-_16") (pintype "power_in"))
      (node (ref "CN4") (pin "18") (pinfunction "PHASE_B_CURRENT_-_18") (pintype "power_in"))
      (node (ref "CN4") (pin "2") (pinfunction "GND_2") (pintype "power_in"))
      (node (ref "CN4") (pin "20") (pinfunction "PHASE_C_CURRENT_-_20") (pintype "power_in"))
      (node (ref "CN4") (pin "22") (pinfunction "GND_22") (pintype "power_in"))
      (node (ref "CN4") (pin "4") (pinfunction "GND_4") (pintype "power_in"))
      (node (ref "CN4") (pin "6") (pinfunction "GND_6") (pintype "power_in"))
      (node (ref "CN4") (pin "8") (pinfunction "GND_8") (pintype "power_in"))
      (node (ref "R112") (pin "2") (pinfunction "2_2") (pintype "passive"))
    )
    (net (code "91") (name "Net-(CN4-PHASE_B_CURRENT_+)") (class "Default")
      (node (ref "CN4") (pin "17") (pinfunction "PHASE_B_CURRENT_+_17") (pintype "output"))
      (node (ref "R97") (pin "1") (pinfunction "1_1") (pintype "passive"))
    )
    (net (code "92") (name "Net-(CN4-PHASE_C_CURRENT_+)") (class "Default")
      (node (ref "CN4") (pin "19") (pinfunction "PHASE_C_CURRENT_+_19") (pintype "output"))
      (node (ref "R101") (pin "1") (pinfunction "1_1") (pintype "passive"))
    )
    (net (code "93") (name "Net-(JP2-NO)") (class "Default")
      (node (ref "C11") (pin "2") (pinfunction "2_2") (pintype "passive"))
      (node (ref "JP2") (pin "2") (pinfunction "NO_2") (pintype "passive"))
    )
    (net (code "94") (name "Net-(JP7-NO)") (class "Default")
      (node (ref "C34") (pin "2") (pinfunction "2_2") (pintype "passive"))
      (node (ref "JP7") (pin "2") (pinfunction "NO_2") (pintype "passive"))
    )
    (net (code "95") (name "Net-(OAM1-Pad1)") (class "Default")
      (node (ref "OAM1") (pin "1") (pintype "passive"))
      (node (ref "R113") (pin "2") (pinfunction "2_2") (pintype "passive"))
    )
    (net (code "96") (name "Net-(OAM1-Pad3)") (class "Default")
      (node (ref "OAM1") (pin "3") (pintype "passive"))
      (node (ref "R84") (pin "2") (pinfunction "2_2") (pintype "passive"))
    )
    (net (code "97") (name "Net-(OAM1-Pad4)") (class "Default")
      (node (ref "OAM1") (pin "4") (pintype "passive"))
      (node (ref "R116") (pin "2") (pinfunction "2_2") (pintype "passive"))
      (node (ref "SB2") (pin "1") (pinfunction "1_1") (pintype "passive"))
    )
    (net (code "98") (name "Net-(OAM1-Pad6)") (class "Default")
      (node (ref "OAM1") (pin "6") (pintype "passive"))
      (node (ref "R77") (pin "2") (pinfunction "2_2") (pintype "passive"))
    )
    (net (code "99") (name "Net-(OAM1-Pad9)") (class "Default")
      (node (ref "OAM1") (pin "9") (pintype "passive"))
      (node (ref "R85") (pin "1") (pinfunction "1_1") (pintype "passive"))
    )
    (net (code "100") (name "Net-(OAM2-Pad3)") (class "Default")
      (node (ref "OAM2") (pin "3") (pintype "passive"))
      (node (ref "R100") (pin "2") (pinfunction "2_2") (pintype "passive"))
    )
    (net (code "101") (name "Net-(OAM2-Pad4)") (class "Default")
      (node (ref "OAM2") (pin "4") (pintype "passive"))
      (node (ref "R132") (pin "2") (pinfunction "2_2") (pintype "passive"))
      (node (ref "SB5") (pin "1") (pinfunction "1_1") (pintype "passive"))
    )
    (net (code "102") (name "Net-(OAM2-Pad6)") (class "Default")
      (node (ref "OAM2") (pin "6") (pintype "passive"))
      (node (ref "R96") (pin "2") (pinfunction "2_2") (pintype "passive"))
    )
    (net (code "103") (name "Net-(OAM2-Pad7)") (class "Default")
      (node (ref "OAM2") (pin "7") (pintype "passive"))
      (node (ref "R134") (pin "2") (pinfunction "2_2") (pintype "passive"))
    )
    (net (code "104") (name "Net-(OAM2-Pad9)") (class "Default")
      (node (ref "OAM2") (pin "9") (pintype "passive"))
      (node (ref "R92") (pin "2") (pinfunction "2_2") (pintype "passive"))
    )
    (net (code "105") (name "Net-(PG3SA-Pad1)") (class "Default")
      (node (ref "PG3SA") (pin "1") (pintype "passive"))
      (node (ref "PG3SA") (pin "6") (pintype "passive"))
      (node (ref "PGM1") (pin "9") (pintype "passive"))
    )
    (net (code "106") (name "Net-(PG3SA-Pad3)") (class "Default")
      (node (ref "PG3SA") (pin "3") (pintype "passive"))
      (node (ref "PG3SA") (pin "4") (pintype "passive"))
      (node (ref "PGM2") (pin "3") (pintype "passive"))
    )
    (net (code "107") (name "Net-(PGM1-Pad2)") (class "Default")
      (node (ref "PGM1") (pin "2") (pintype "passive"))
      (node (ref "R93") (pin "2") (pinfunction "2_2") (pintype "passive"))
    )
    (net (code "108") (name "Net-(PGM1-Pad5)") (class "Default")
      (node (ref "PGM1") (pin "5") (pintype "passive"))
      (node (ref "R95") (pin "2") (pinfunction "2_2") (pintype "passive"))
    )
    (net (code "109") (name "Net-(PGM1-Pad8)") (class "Default")
      (node (ref "PGM1") (pin "8") (pintype "passive"))
      (node (ref "R94") (pin "2") (pinfunction "2_2") (pintype "passive"))
    )
    (net (code "110") (name "Net-(PGM2-Pad2)") (class "Default")
      (node (ref "PGM2") (pin "2") (pintype "passive"))
      (node (ref "R128") (pin "2") (pinfunction "2_2") (pintype "passive"))
    )
    (net (code "111") (name "Net-(PGM2-Pad5)") (class "Default")
      (node (ref "PGM2") (pin "5") (pintype "passive"))
      (node (ref "R109") (pin "2") (pinfunction "2_2") (pintype "passive"))
    )
    (net (code "112") (name "Net-(PGM2-Pad8)") (class "Default")
      (node (ref "PGM2") (pin "8") (pintype "passive"))
      (node (ref "R120") (pin "2") (pinfunction "2_2") (pintype "passive"))
    )
    (net (code "113") (name "Net-(R107-Pad1)") (class "Default")
      (node (ref "R107") (pin "1") (pinfunction "1_1") (pintype "passive"))
      (node (ref "R132") (pin "1") (pinfunction "1_1") (pintype "passive"))
    )
    (net (code "114") (name "Net-(R108-Pad1)") (class "Default")
      (node (ref "R108") (pin "1") (pinfunction "1_1") (pintype "passive"))
      (node (ref "R134") (pin "1") (pinfunction "1_1") (pintype "passive"))
      (node (ref "SB5") (pin "2") (pinfunction "2_2") (pintype "passive"))
    )
    (net (code "115") (name "Net-(R113-Pad1)") (class "Default")
      (node (ref "R113") (pin "1") (pinfunction "1_1") (pintype "passive"))
      (node (ref "R98") (pin "1") (pinfunction "1_1") (pintype "passive"))
      (node (ref "SB2") (pin "2") (pinfunction "2_2") (pintype "passive"))
    )
    (net (code "116") (name "Net-(R116-Pad1)") (class "Default")
      (node (ref "R116") (pin "1") (pinfunction "1_1") (pintype "passive"))
      (node (ref "R83") (pin "1") (pinfunction "1_1") (pintype "passive"))
    )
    (net (code "117") (name "unconnected-(OAM1-Pad10)") (class "Default")
      (node (ref "OAM1") (pin "10") (pintype "passive"))
    )
    (net (code "118") (name "unconnected-(OAM1-Pad11)") (class "Default")
      (node (ref "OAM1") (pin "11") (pintype "passive"))
    )
    (net (code "119") (name "unconnected-(OAM1-Pad12)") (class "Default")
      (node (ref "OAM1") (pin "12") (pintype "passive"))
    )
    (net (code "120") (name "unconnected-(OAM2-Pad10)") (class "Default")
      (node (ref "OAM2") (pin "10") (pintype "passive"))
    )
    (net (code "121") (name "unconnected-(OAM2-Pad11)") (class "Default")
      (node (ref "OAM2") (pin "11") (pintype "passive"))
    )
    (net (code "122") (name "unconnected-(OAM2-Pad12)") (class "Default")
      (node (ref "OAM2") (pin "12") (pintype "passive"))
    )
    (net (code "123") (name "unconnected-(PGM1-Pad10)") (class "Default")
      (node (ref "PGM1") (pin "10") (pintype "passive"))
    )
    (net (code "124") (name "unconnected-(PGM1-Pad11)") (class "Default")
      (node (ref "PGM1") (pin "11") (pintype "passive"))
    )
    (net (code "125") (name "unconnected-(PGM1-Pad12)") (class "Default")
      (node (ref "PGM1") (pin "12") (pintype "passive"))
    )
    (net (code "126") (name "unconnected-(PGM2-Pad10)") (class "Default")
      (node (ref "PGM2") (pin "10") (pintype "passive"))
    )
    (net (code "127") (name "unconnected-(PGM2-Pad11)") (class "Default")
      (node (ref "PGM2") (pin "11") (pintype "passive"))
    )
    (net (code "128") (name "unconnected-(PGM2-Pad12)") (class "Default")
      (node (ref "PGM2") (pin "12") (pintype "passive"))
    )
  )
)
